# ST7735_Extend.net
KiCad netlist of a schematic drawn in Altium Designer
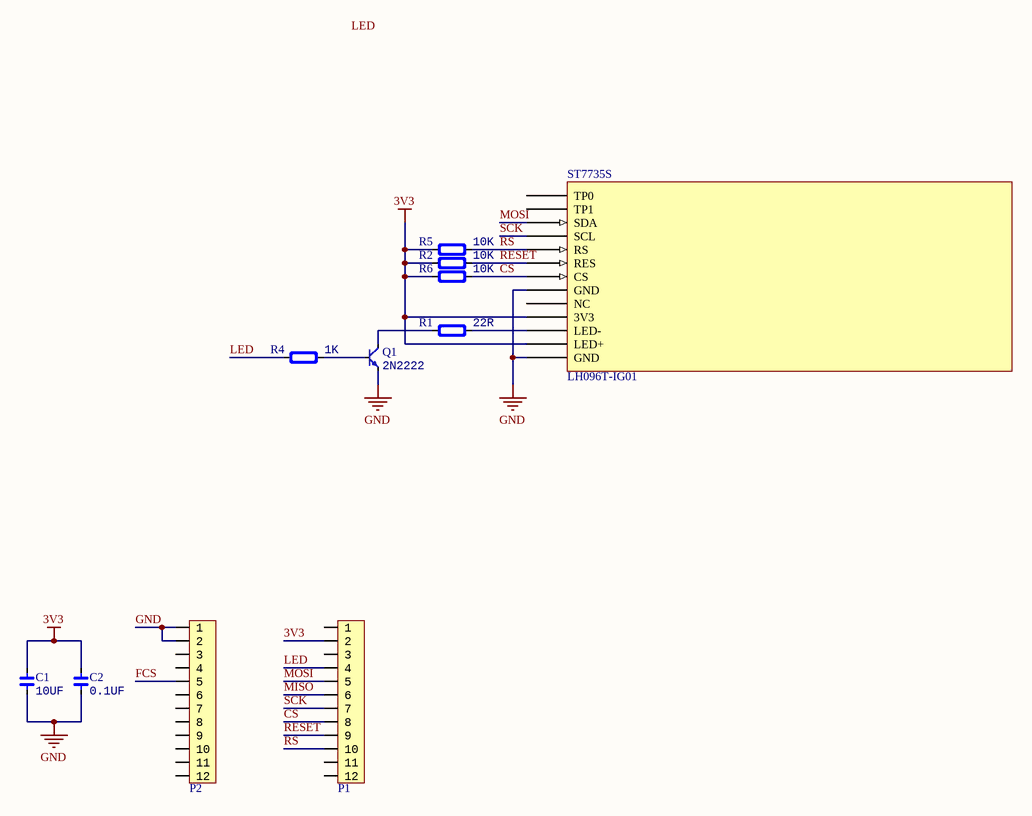
[diagram p0: ST7735_Extend.SchDoc]

(export (version "E")
  (design (tool "Eeschema 10.0.6"))
  (components
    (comp (ref "C1")
      (value "10UF")
      (footprint "PCB_PassiveCap:CAP_0603")
      (description "Capacitor")
      (fields (field (name "Comment") "C0603"))
      (libsource (lib "SCH_Passive") (part "Cap_0603"))
    )
    (comp (ref "C2")
      (value "0.1UF")
      (footprint "PCB_PassiveCap:CAP_0603")
      (description "Capacitor")
      (fields (field (name "Comment") "C0603"))
      (libsource (lib "SCH_Passive") (part "Cap_0603"))
    )
    (comp (ref "P1")
      (value "HDR1x12_2.54")
      (footprint "PCB_ConnectorHDR:HDR1X12_2.54_180F")
      (description "Header")
      (libsource (lib "SCH_ConnectorHDR") (part "HDR1x12_2.54"))
    )
    (comp (ref "P2")
      (value "HDR1x12_2.54")
      (footprint "PCB_ConnectorHDR:HDR1X12_2.54_180F")
      (description "Header")
      (libsource (lib "SCH_ConnectorHDR") (part "HDR1x12_2.54"))
    )
    (comp (ref "Q1")
      (value "2N2222")
      (footprint "PCB_IntegratedCircuit:SOT23-3")
      (description "Transistor")
      (libsource (lib "SCH_Active") (part "BJT_NPN"))
    )
    (comp (ref "R1")
      (value "22R")
      (footprint "PCB_PassiveRes:RES_0603")
      (description "Resistor")
      (fields (field (name "Comment") "R0603"))
      (libsource (lib "SCH_Passive") (part "Res_0603"))
    )
    (comp (ref "R2")
      (value "10K")
      (footprint "PCB_PassiveRes:RES_0603")
      (description "Resistor")
      (fields (field (name "Comment") "R0603"))
      (libsource (lib "SCH_Passive") (part "Res_0603"))
    )
    (comp (ref "R4")
      (value "1K")
      (footprint "PCB_PassiveRes:RES_0603")
      (description "Resistor")
      (fields (field (name "Comment") "R0603"))
      (libsource (lib "SCH_Passive") (part "Res_0603"))
    )
    (comp (ref "R5")
      (value "10K")
      (footprint "PCB_PassiveRes:RES_0603")
      (description "Resistor")
      (fields (field (name "Comment") "R0603"))
      (libsource (lib "SCH_Passive") (part "Res_0603"))
    )
    (comp (ref "R6")
      (value "10K")
      (footprint "PCB_PassiveRes:RES_0603")
      (description "Resistor")
      (fields (field (name "Comment") "R0603"))
      (libsource (lib "SCH_Passive") (part "Res_0603"))
    )
    (comp (ref "ST7735S")
      (value "LH096T-IG01")
      (footprint "LH096T-IG01")
      (libsource (lib "Schlib1") (part "LH096T-IG01"))
    )
  )
  (nets
    (net (code "1") (name "/CS") (class "Default")
      (node (ref "P1") (pin "8") (pinfunction "8_8") (pintype "passive"))
      (node (ref "R6") (pin "2") (pinfunction "2_2") (pintype "passive"))
      (node (ref "ST7735S") (pin "6") (pinfunction "CS_6") (pintype "input"))
    )
    (net (code "2") (name "/FCS") (class "Default")
      (node (ref "P2") (pin "5") (pinfunction "5_5") (pintype "passive"))
    )
    (net (code "3") (name "/LED") (class "Default")
      (node (ref "P1") (pin "4") (pinfunction "4_4") (pintype "passive"))
      (node (ref "R4") (pin "1") (pinfunction "1_1") (pintype "passive"))
    )
    (net (code "4") (name "/MISO") (class "Default")
      (node (ref "P1") (pin "6") (pinfunction "6_6") (pintype "passive"))
    )
    (net (code "5") (name "/MOSI") (class "Default")
      (node (ref "P1") (pin "5") (pinfunction "5_5") (pintype "passive"))
      (node (ref "ST7735S") (pin "2") (pinfunction "SDA_2") (pintype "input"))
    )
    (net (code "6") (name "/RESET") (class "Default")
      (node (ref "P1") (pin "9") (pinfunction "9_9") (pintype "passive"))
      (node (ref "R2") (pin "2") (pinfunction "2_2") (pintype "passive"))
      (node (ref "ST7735S") (pin "5") (pinfunction "RES_5") (pintype "input"))
    )
    (net (code "7") (name "/RS") (class "Default")
      (node (ref "P1") (pin "10") (pinfunction "10_10") (pintype "passive"))
      (node (ref "R5") (pin "2") (pinfunction "2_2") (pintype "passive"))
      (node (ref "ST7735S") (pin "4") (pinfunction "RS_4") (pintype "input"))
    )
    (net (code "8") (name "/SCK") (class "Default")
      (node (ref "P1") (pin "7") (pinfunction "7_7") (pintype "passive"))
      (node (ref "ST7735S") (pin "3") (pinfunction "SCL_3") (pintype "passive"))
    )
    (net (code "9") (name "3V3") (class "Default")
      (node (ref "C1") (pin "2") (pinfunction "2_2") (pintype "passive"))
      (node (ref "C2") (pin "2") (pinfunction "2_2") (pintype "passive"))
      (node (ref "P1") (pin "2") (pinfunction "2_2") (pintype "passive"))
      (node (ref "R2") (pin "1") (pinfunction "1_1") (pintype "passive"))
      (node (ref "R5") (pin "1") (pinfunction "1_1") (pintype "passive"))
      (node (ref "R6") (pin "1") (pinfunction "1_1") (pintype "passive"))
      (node (ref "ST7735S") (pin "11") (pinfunction "LED+_11") (pintype "power_in"))
      (node (ref "ST7735S") (pin "9") (pinfunction "3V3_9") (pintype "power_in"))
    )
    (net (code "10") (name "GND") (class "Default")
      (node (ref "C1") (pin "1") (pinfunction "1_1") (pintype "passive"))
      (node (ref "C2") (pin "1") (pinfunction "1_1") (pintype "passive"))
      (node (ref "P2") (pin "1") (pinfunction "1_1") (pintype "passive"))
      (node (ref "P2") (pin "2") (pinfunction "2_2") (pintype "passive"))
      (node (ref "Q1") (pin "2") (pinfunction "E_2") (pintype "passive"))
      (node (ref "ST7735S") (pin "12") (pinfunction "GND_12") (pintype "power_in"))
      (node (ref "ST7735S") (pin "7") (pinfunction "GND_7") (pintype "power_in"))
    )
    (net (code "11") (name "Net-(Q1-B)") (class "Default")
      (node (ref "Q1") (pin "1") (pinfunction "B_1") (pintype "passive"))
      (node (ref "R4") (pin "2") (pinfunction "2_2") (pintype "passive"))
    )
    (net (code "12") (name "Net-(Q1-C)") (class "Default")
      (node (ref "Q1") (pin "3") (pinfunction "C_3") (pintype "passive"))
      (node (ref "R1") (pin "1") (pinfunction "1_1") (pintype "passive"))
    )
    (net (code "13") (name "Net-(ST7735S-LED-)") (class "Default")
      (node (ref "R1") (pin "2") (pinfunction "2_2") (pintype "passive"))
      (node (ref "ST7735S") (pin "10") (pinfunction "LED-_10") (pintype "power_in"))
    )
    (net (code "14") (name "unconnected-(P1-Pad1)") (class "Default")
      (node (ref "P1") (pin "1") (pinfunction "1_1") (pintype "passive"))
    )
    (net (code "15") (name "unconnected-(P1-Pad3)") (class "Default")
      (node (ref "P1") (pin "3") (pinfunction "3_3") (pintype "passive"))
    )
    (net (code "16") (name "unconnected-(P1-Pad11)") (class "Default")
      (node (ref "P1") (pin "11") (pinfunction "11_11") (pintype "passive"))
    )
    (net (code "17") (name "unconnected-(P1-Pad12)") (class "Default")
      (node (ref "P1") (pin "12") (pinfunction "12_12") (pintype "passive"))
    )
    (net (code "18") (name "unconnected-(P2-Pad3)") (class "Default")
      (node (ref "P2") (pin "3") (pinfunction "3_3") (pintype "passive"))
    )
    (net (code "19") (name "unconnected-(P2-Pad4)") (class "Default")
      (node (ref "P2") (pin "4") (pinfunction "4_4") (pintype "passive"))
    )
    (net (code "20") (name "unconnected-(P2-Pad6)") (class "Default")
      (node (ref "P2") (pin "6") (pinfunction "6_6") (pintype "passive"))
    )
    (net (code "21") (name "unconnected-(P2-Pad7)") (class "Default")
      (node (ref "P2") (pin "7") (pinfunction "7_7") (pintype "passive"))
    )
    (net (code "22") (name "unconnected-(P2-Pad8)") (class "Default")
      (node (ref "P2") (pin "8") (pinfunction "8_8") (pintype "passive"))
    )
    (net (code "23") (name "unconnected-(P2-Pad9)") (class "Default")
      (node (ref "P2") (pin "9") (pinfunction "9_9") (pintype "passive"))
    )
    (net (code "24") (name "unconnected-(P2-Pad10)") (class "Default")
      (node (ref "P2") (pin "10") (pinfunction "10_10") (pintype "passive"))
    )
    (net (code "25") (name "unconnected-(P2-Pad11)") (class "Default")
      (node (ref "P2") (pin "11") (pinfunction "11_11") (pintype "passive"))
    )
    (net (code "26") (name "unconnected-(P2-Pad12)") (class "Default")
      (node (ref "P2") (pin "12") (pinfunction "12_12") (pintype "passive"))
    )
    (net (code "27") (name "unconnected-(ST7735S-NC-Pad8)") (class "Default")
      (node (ref "ST7735S") (pin "8") (pinfunction "NC_8") (pintype "passive"))
    )
    (net (code "28") (name "unconnected-(ST7735S-TP0-Pad0)") (class "Default")
      (node (ref "ST7735S") (pin "0") (pinfunction "TP0_0") (pintype "passive"))
    )
    (net (code "29") (name "unconnected-(ST7735S-TP1-Pad1)") (class "Default")
      (node (ref "ST7735S") (pin "1") (pinfunction "TP1_1") (pintype "passive"))
    )
  )
)
